# smogbusters.net
KiCad netlist of a schematic drawn in EAGLE
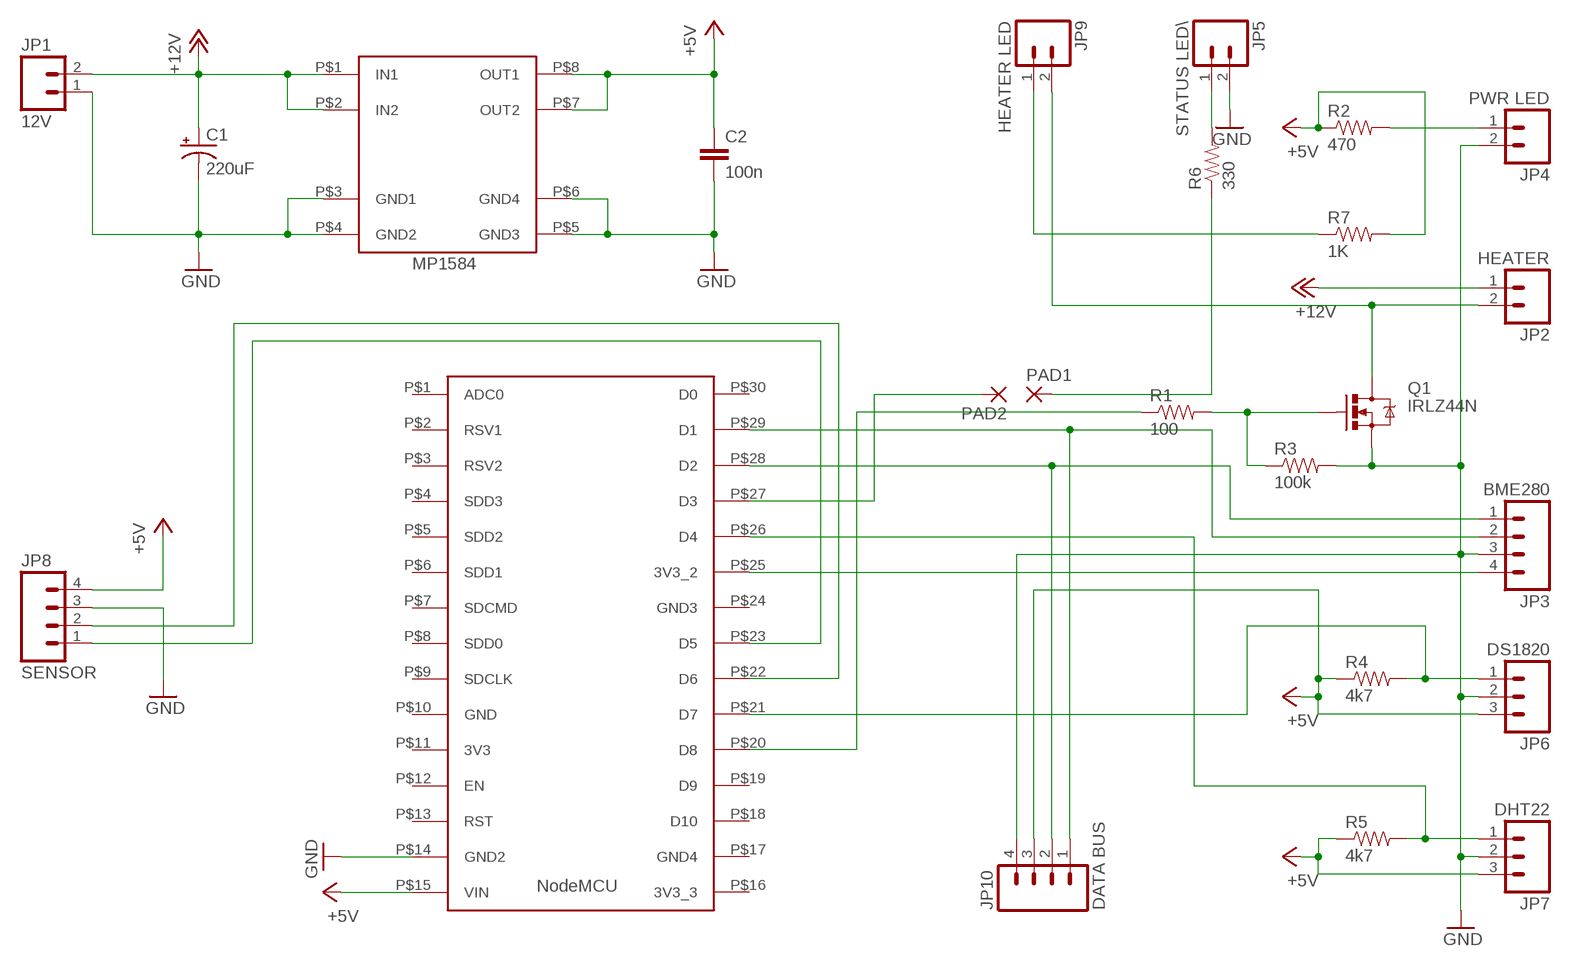
[diagram p0: schematic, sheet 1]

(export (version "E")
  (design (tool "Eeschema 10.0.6"))
  (components
    (comp (ref "C1")
      (value "220uF")
      (footprint "eagle-import:CPOL-RADIAL-100UF-25V")
      (libsource (lib "eagle-import") (part "CAP_POLPTH1"))
    )
    (comp (ref "C2")
      (value "100n")
      (footprint "eagle-import:C5B2.5")
      (libsource (lib "eagle-import") (part "C5/2.5"))
    )
    (comp (ref "JP1")
      (value "12V")
      (footprint "eagle-import:SCREWTERMINAL-5MM-2")
      (libsource (lib "eagle-import") (part "M025MM"))
    )
    (comp (ref "JP2")
      (value "HEATER")
      (footprint "eagle-import:SCREWTERMINAL-5MM-2")
      (libsource (lib "eagle-import") (part "M025MM"))
    )
    (comp (ref "JP3")
      (value "BME280")
      (footprint "eagle-import:1X04")
      (libsource (lib "eagle-import") (part "M04PTH"))
    )
    (comp (ref "JP4")
      (value "PWR LED")
      (footprint "eagle-import:1X02")
      (libsource (lib "eagle-import") (part "M02PTH"))
    )
    (comp (ref "JP5")
      (value "STATUS LED\\")
      (footprint "eagle-import:1X02")
      (libsource (lib "eagle-import") (part "M02PTH"))
    )
    (comp (ref "JP6")
      (value "DS1820")
      (footprint "eagle-import:1X03")
      (libsource (lib "eagle-import") (part "M03PTH"))
    )
    (comp (ref "JP7")
      (value "DHT22")
      (footprint "eagle-import:1X03")
      (libsource (lib "eagle-import") (part "M03PTH"))
    )
    (comp (ref "JP8")
      (value "SENSOR")
      (footprint "eagle-import:MOLEX-1X4")
      (libsource (lib "eagle-import") (part "M04POLAR"))
    )
    (comp (ref "JP9")
      (value "HEATER LED")
      (footprint "eagle-import:1X02")
      (libsource (lib "eagle-import") (part "M02PTH"))
    )
    (comp (ref "JP10")
      (value "DATA BUS")
      (footprint "eagle-import:1X04")
      (libsource (lib "eagle-import") (part "M04PTH"))
    )
    (comp (ref "PAD1")
      (value "1,6/0,8")
      (footprint "eagle-import:1,6_0,8")
      (libsource (lib "eagle-import") (part "1,6/0,8"))
    )
    (comp (ref "PAD2")
      (value "1,6/0,8")
      (footprint "eagle-import:1,6_0,8")
      (libsource (lib "eagle-import") (part "1,6/0,8"))
    )
    (comp (ref "Q1")
      (value "IRLZ44N")
      (footprint "eagle-import:TO220V")
      (libsource (lib "eagle-import") (part "MOSFET-NCHANNELFQP30N06L"))
    )
    (comp (ref "R1")
      (value "100")
      (footprint "eagle-import:AXIAL-0.3")
      (libsource (lib "eagle-import") (part "1KOHM-1/4W-1%(PTH)"))
    )
    (comp (ref "R2")
      (value "470")
      (footprint "eagle-import:AXIAL-0.3")
      (libsource (lib "eagle-import") (part "1KOHM-1/4W-1%(PTH)"))
    )
    (comp (ref "R3")
      (value "100k")
      (footprint "eagle-import:AXIAL-0.3")
      (libsource (lib "eagle-import") (part "1KOHM-1/4W-1%(PTH)"))
    )
    (comp (ref "R4")
      (value "4k7")
      (footprint "eagle-import:AXIAL-0.3")
      (libsource (lib "eagle-import") (part "1KOHM-1/4W-1%(PTH)"))
    )
    (comp (ref "R5")
      (value "4k7")
      (footprint "eagle-import:AXIAL-0.3")
      (libsource (lib "eagle-import") (part "1KOHM-1/4W-1%(PTH)"))
    )
    (comp (ref "R6")
      (value "330")
      (footprint "eagle-import:AXIAL-0.3")
      (libsource (lib "eagle-import") (part "1KOHM-1/4W-1%(PTH)"))
    )
    (comp (ref "R7")
      (value "1K")
      (footprint "eagle-import:AXIAL-0.3")
      (libsource (lib "eagle-import") (part "1KOHM-1/4W-1%(PTH)"))
    )
    (comp (ref "U$1")
      (value "NODEMCU")
      (footprint "eagle-import:NODEMCU")
      (libsource (lib "eagle-import") (part "NODEMCU"))
    )
    (comp (ref "U$2")
      (value "MP1584")
      (footprint "eagle-import:MP1584")
      (libsource (lib "eagle-import") (part "MP1584"))
    )
  )
  (nets
    (net (code "1") (name "+5V") (class "Default")
      (node (ref "C2") (pin "1") (pinfunction "1_1") (pintype "passive"))
      (node (ref "JP10") (pin "3") (pinfunction "3_3") (pintype "passive"))
      (node (ref "JP6") (pin "3") (pinfunction "3_3") (pintype "passive"))
      (node (ref "JP7") (pin "3") (pinfunction "3_3") (pintype "passive"))
      (node (ref "JP8") (pin "4") (pinfunction "4_4") (pintype "passive"))
      (node (ref "R2") (pin "P$1") (pinfunction "1_P$1") (pintype "passive"))
      (node (ref "R4") (pin "P$1") (pinfunction "1_P$1") (pintype "passive"))
      (node (ref "R5") (pin "P$1") (pinfunction "1_P$1") (pintype "passive"))
      (node (ref "R7") (pin "P$2") (pinfunction "2_P$2") (pintype "passive"))
      (node (ref "U$1") (pin "P$15") (pinfunction "VIN_P$15") (pintype "bidirectional"))
      (node (ref "U$2") (pin "P$7") (pinfunction "OUT2_P$7") (pintype "bidirectional"))
      (node (ref "U$2") (pin "P$8") (pinfunction "OUT1_P$8") (pintype "bidirectional"))
    )
    (net (code "2") (name "+12V") (class "Default")
      (node (ref "C1") (pin "1") (pinfunction "+_1") (pintype "passive"))
      (node (ref "JP1") (pin "2") (pinfunction "2_2") (pintype "passive"))
      (node (ref "JP2") (pin "1") (pinfunction "1_1") (pintype "passive"))
      (node (ref "U$2") (pin "P$1") (pinfunction "IN1_P$1") (pintype "input"))
      (node (ref "U$2") (pin "P$2") (pinfunction "IN2_P$2") (pintype "input"))
    )
    (net (code "3") (name "GND") (class "Default")
      (node (ref "C1") (pin "2") (pinfunction "-_2") (pintype "passive"))
      (node (ref "C2") (pin "2") (pinfunction "2_2") (pintype "passive"))
      (node (ref "JP1") (pin "1") (pinfunction "1_1") (pintype "passive"))
      (node (ref "JP10") (pin "4") (pinfunction "4_4") (pintype "passive"))
      (node (ref "JP3") (pin "3") (pinfunction "3_3") (pintype "passive"))
      (node (ref "JP4") (pin "2") (pinfunction "2_2") (pintype "passive"))
      (node (ref "JP5") (pin "2") (pinfunction "2_2") (pintype "passive"))
      (node (ref "JP6") (pin "2") (pinfunction "2_2") (pintype "passive"))
      (node (ref "JP7") (pin "2") (pinfunction "2_2") (pintype "passive"))
      (node (ref "JP8") (pin "3") (pinfunction "3_3") (pintype "passive"))
      (node (ref "Q1") (pin "3") (pinfunction "S_3") (pintype "passive"))
      (node (ref "R3") (pin "P$2") (pinfunction "2_P$2") (pintype "passive"))
      (node (ref "U$1") (pin "P$14") (pinfunction "GND2_P$14") (pintype "bidirectional"))
      (node (ref "U$2") (pin "P$3") (pinfunction "GND1_P$3") (pintype "bidirectional"))
      (node (ref "U$2") (pin "P$4") (pinfunction "GND2_P$4") (pintype "bidirectional"))
      (node (ref "U$2") (pin "P$5") (pinfunction "GND3_P$5") (pintype "bidirectional"))
      (node (ref "U$2") (pin "P$6") (pinfunction "GND4_P$6") (pintype "bidirectional"))
    )
    (net (code "4") (name "Net-(PAD1-P)") (class "Default")
      (node (ref "PAD1") (pin "1") (pinfunction "P_1") (pintype "passive"))
      (node (ref "R6") (pin "P$1") (pinfunction "1_P$1") (pintype "passive"))
    )
    (net (code "5") (name "Net-(PAD2-P)") (class "Default")
      (node (ref "PAD2") (pin "1") (pinfunction "P_1") (pintype "passive"))
      (node (ref "U$1") (pin "P$27") (pinfunction "D3_P$27") (pintype "bidirectional"))
    )
    (net (code "6") (name "Net-(Q1-D)") (class "Default")
      (node (ref "JP2") (pin "2") (pinfunction "2_2") (pintype "passive"))
      (node (ref "JP9") (pin "2") (pinfunction "2_2") (pintype "passive"))
      (node (ref "Q1") (pin "2") (pinfunction "D_2") (pintype "passive"))
    )
    (net (code "7") (name "Net-(Q1-G)") (class "Default")
      (node (ref "Q1") (pin "1") (pinfunction "G_1") (pintype "passive"))
      (node (ref "R1") (pin "P$2") (pinfunction "2_P$2") (pintype "passive"))
      (node (ref "R3") (pin "P$1") (pinfunction "1_P$1") (pintype "passive"))
    )
    (net (code "8") (name "Net-(R1-1)") (class "Default")
      (node (ref "R1") (pin "P$1") (pinfunction "1_P$1") (pintype "passive"))
      (node (ref "U$1") (pin "P$20") (pinfunction "D8_P$20") (pintype "bidirectional"))
    )
    (net (code "9") (name "Net-(R2-2)") (class "Default")
      (node (ref "JP4") (pin "1") (pinfunction "1_1") (pintype "passive"))
      (node (ref "R2") (pin "P$2") (pinfunction "2_P$2") (pintype "passive"))
    )
    (net (code "10") (name "Net-(R4-2)") (class "Default")
      (node (ref "JP6") (pin "1") (pinfunction "1_1") (pintype "passive"))
      (node (ref "R4") (pin "P$2") (pinfunction "2_P$2") (pintype "passive"))
      (node (ref "U$1") (pin "P$21") (pinfunction "D7_P$21") (pintype "bidirectional"))
    )
    (net (code "11") (name "Net-(R5-2)") (class "Default")
      (node (ref "JP7") (pin "1") (pinfunction "1_1") (pintype "passive"))
      (node (ref "R5") (pin "P$2") (pinfunction "2_P$2") (pintype "passive"))
      (node (ref "U$1") (pin "P$26") (pinfunction "D4_P$26") (pintype "bidirectional"))
    )
    (net (code "12") (name "Net-(R6-2)") (class "Default")
      (node (ref "JP5") (pin "1") (pinfunction "1_1") (pintype "passive"))
      (node (ref "R6") (pin "P$2") (pinfunction "2_P$2") (pintype "passive"))
    )
    (net (code "13") (name "Net-(R7-1)") (class "Default")
      (node (ref "JP9") (pin "1") (pinfunction "1_1") (pintype "passive"))
      (node (ref "R7") (pin "P$1") (pinfunction "1_P$1") (pintype "passive"))
    )
    (net (code "14") (name "Net-(U$1-3V3_2)") (class "Default")
      (node (ref "JP3") (pin "4") (pinfunction "4_4") (pintype "passive"))
      (node (ref "U$1") (pin "P$25") (pinfunction "3V3_2_P$25") (pintype "bidirectional"))
    )
    (net (code "15") (name "Net-(U$1-D1)") (class "Default")
      (node (ref "JP10") (pin "1") (pinfunction "1_1") (pintype "passive"))
      (node (ref "JP3") (pin "2") (pinfunction "2_2") (pintype "passive"))
      (node (ref "U$1") (pin "P$29") (pinfunction "D1_P$29") (pintype "bidirectional"))
    )
    (net (code "16") (name "Net-(U$1-D2)") (class "Default")
      (node (ref "JP10") (pin "2") (pinfunction "2_2") (pintype "passive"))
      (node (ref "JP3") (pin "1") (pinfunction "1_1") (pintype "passive"))
      (node (ref "U$1") (pin "P$28") (pinfunction "D2_P$28") (pintype "bidirectional"))
    )
    (net (code "17") (name "Net-(U$1-D5)") (class "Default")
      (node (ref "JP8") (pin "1") (pinfunction "1_1") (pintype "passive"))
      (node (ref "U$1") (pin "P$23") (pinfunction "D5_P$23") (pintype "bidirectional"))
    )
    (net (code "18") (name "Net-(U$1-D6)") (class "Default")
      (node (ref "JP8") (pin "2") (pinfunction "2_2") (pintype "passive"))
      (node (ref "U$1") (pin "P$22") (pinfunction "D6_P$22") (pintype "bidirectional"))
    )
    (net (code "19") (name "unconnected-(U$1-3V3-PadP$11)") (class "Default")
      (node (ref "U$1") (pin "P$11") (pinfunction "3V3_P$11") (pintype "bidirectional"))
    )
    (net (code "20") (name "unconnected-(U$1-3V3_3-PadP$16)") (class "Default")
      (node (ref "U$1") (pin "P$16") (pinfunction "3V3_3_P$16") (pintype "bidirectional"))
    )
    (net (code "21") (name "unconnected-(U$1-ADC0-PadP$1)") (class "Default")
      (node (ref "U$1") (pin "P$1") (pinfunction "ADC0_P$1") (pintype "bidirectional"))
    )
    (net (code "22") (name "unconnected-(U$1-D0-PadP$30)") (class "Default")
      (node (ref "U$1") (pin "P$30") (pinfunction "D0_P$30") (pintype "bidirectional"))
    )
    (net (code "23") (name "unconnected-(U$1-D9-PadP$19)") (class "Default")
      (node (ref "U$1") (pin "P$19") (pinfunction "D9_P$19") (pintype "bidirectional"))
    )
    (net (code "24") (name "unconnected-(U$1-D10-PadP$18)") (class "Default")
      (node (ref "U$1") (pin "P$18") (pinfunction "D10_P$18") (pintype "bidirectional"))
    )
    (net (code "25") (name "unconnected-(U$1-EN-PadP$12)") (class "Default")
      (node (ref "U$1") (pin "P$12") (pinfunction "EN_P$12") (pintype "bidirectional"))
    )
    (net (code "26") (name "unconnected-(U$1-GND-PadP$10)") (class "Default")
      (node (ref "U$1") (pin "P$10") (pinfunction "GND_P$10") (pintype "bidirectional"))
    )
    (net (code "27") (name "unconnected-(U$1-GND3-PadP$24)") (class "Default")
      (node (ref "U$1") (pin "P$24") (pinfunction "GND3_P$24") (pintype "bidirectional"))
    )
    (net (code "28") (name "unconnected-(U$1-GND4-PadP$17)") (class "Default")
      (node (ref "U$1") (pin "P$17") (pinfunction "GND4_P$17") (pintype "bidirectional"))
    )
    (net (code "29") (name "unconnected-(U$1-RST-PadP$13)") (class "Default")
      (node (ref "U$1") (pin "P$13") (pinfunction "RST_P$13") (pintype "bidirectional"))
    )
    (net (code "30") (name "unconnected-(U$1-RSV1-PadP$2)") (class "Default")
      (node (ref "U$1") (pin "P$2") (pinfunction "RSV1_P$2") (pintype "bidirectional"))
    )
    (net (code "31") (name "unconnected-(U$1-RSV2-PadP$3)") (class "Default")
      (node (ref "U$1") (pin "P$3") (pinfunction "RSV2_P$3") (pintype "bidirectional"))
    )
    (net (code "32") (name "unconnected-(U$1-SDCLK-PadP$9)") (class "Default")
      (node (ref "U$1") (pin "P$9") (pinfunction "SDCLK_P$9") (pintype "bidirectional"))
    )
    (net (code "33") (name "unconnected-(U$1-SDCMD-PadP$7)") (class "Default")
      (node (ref "U$1") (pin "P$7") (pinfunction "SDCMD_P$7") (pintype "bidirectional"))
    )
    (net (code "34") (name "unconnected-(U$1-SDD0-PadP$8)") (class "Default")
      (node (ref "U$1") (pin "P$8") (pinfunction "SDD0_P$8") (pintype "bidirectional"))
    )
    (net (code "35") (name "unconnected-(U$1-SDD1-PadP$6)") (class "Default")
      (node (ref "U$1") (pin "P$6") (pinfunction "SDD1_P$6") (pintype "bidirectional"))
    )
    (net (code "36") (name "unconnected-(U$1-SDD2-PadP$5)") (class "Default")
      (node (ref "U$1") (pin "P$5") (pinfunction "SDD2_P$5") (pintype "bidirectional"))
    )
    (net (code "37") (name "unconnected-(U$1-SDD3-PadP$4)") (class "Default")
      (node (ref "U$1") (pin "P$4") (pinfunction "SDD3_P$4") (pintype "bidirectional"))
    )
  )
)
